# IronDue.net
KiCad netlist of a schematic drawn in EAGLE
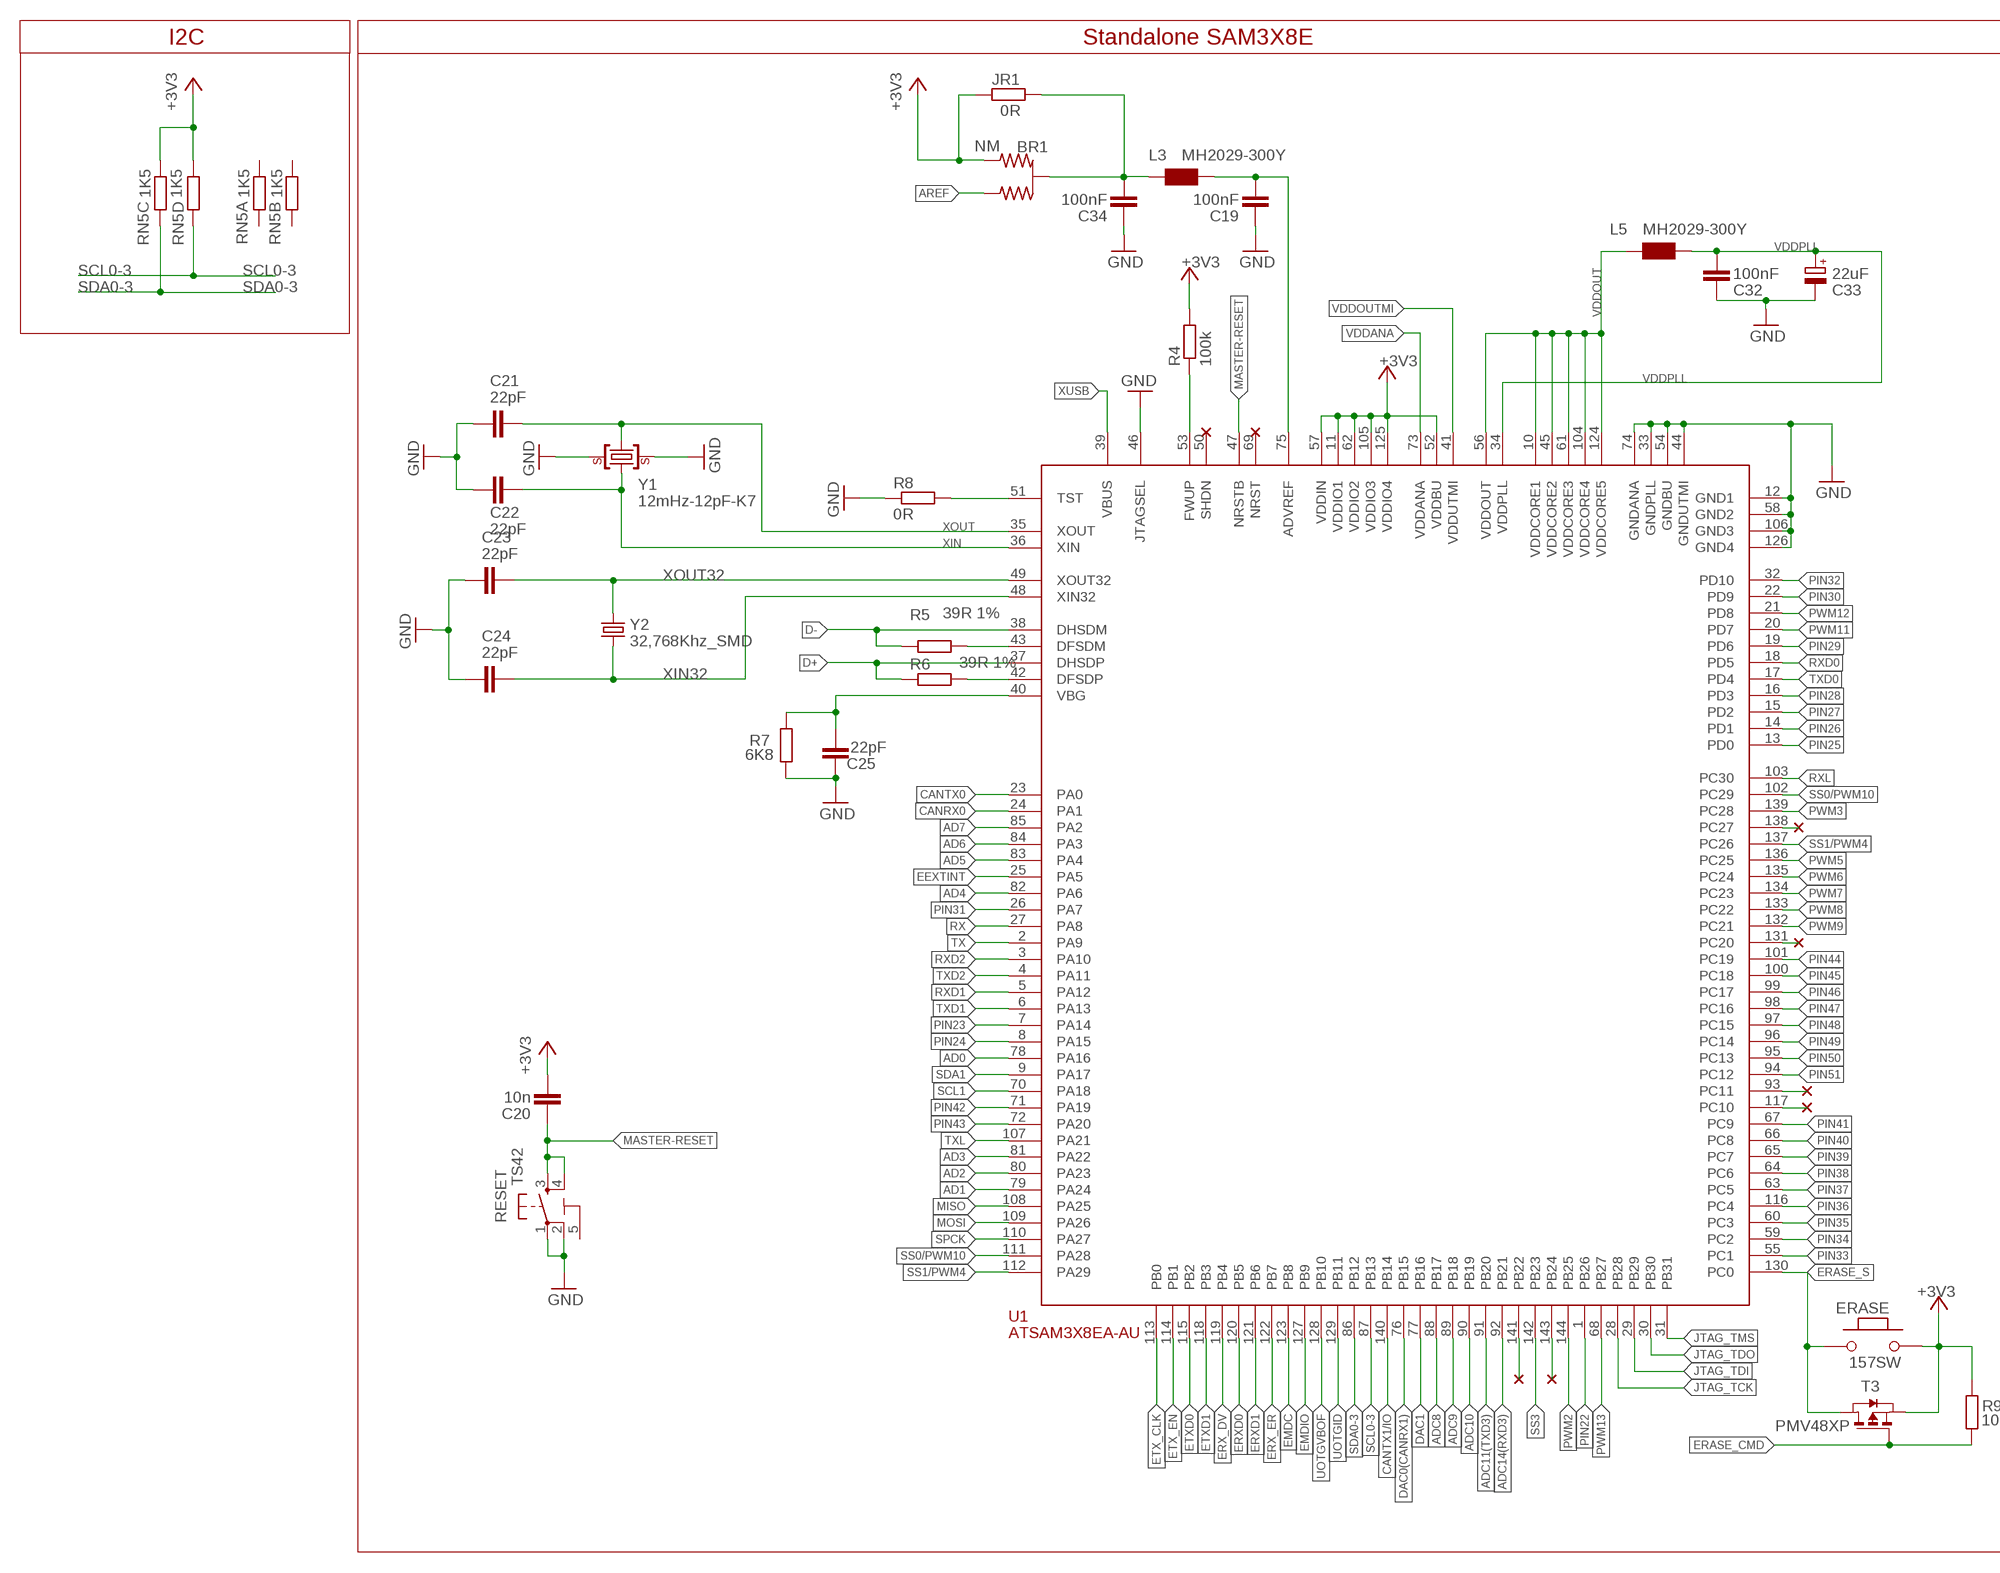
[diagram p0: schematic, sheet 1, part 1 of 2]
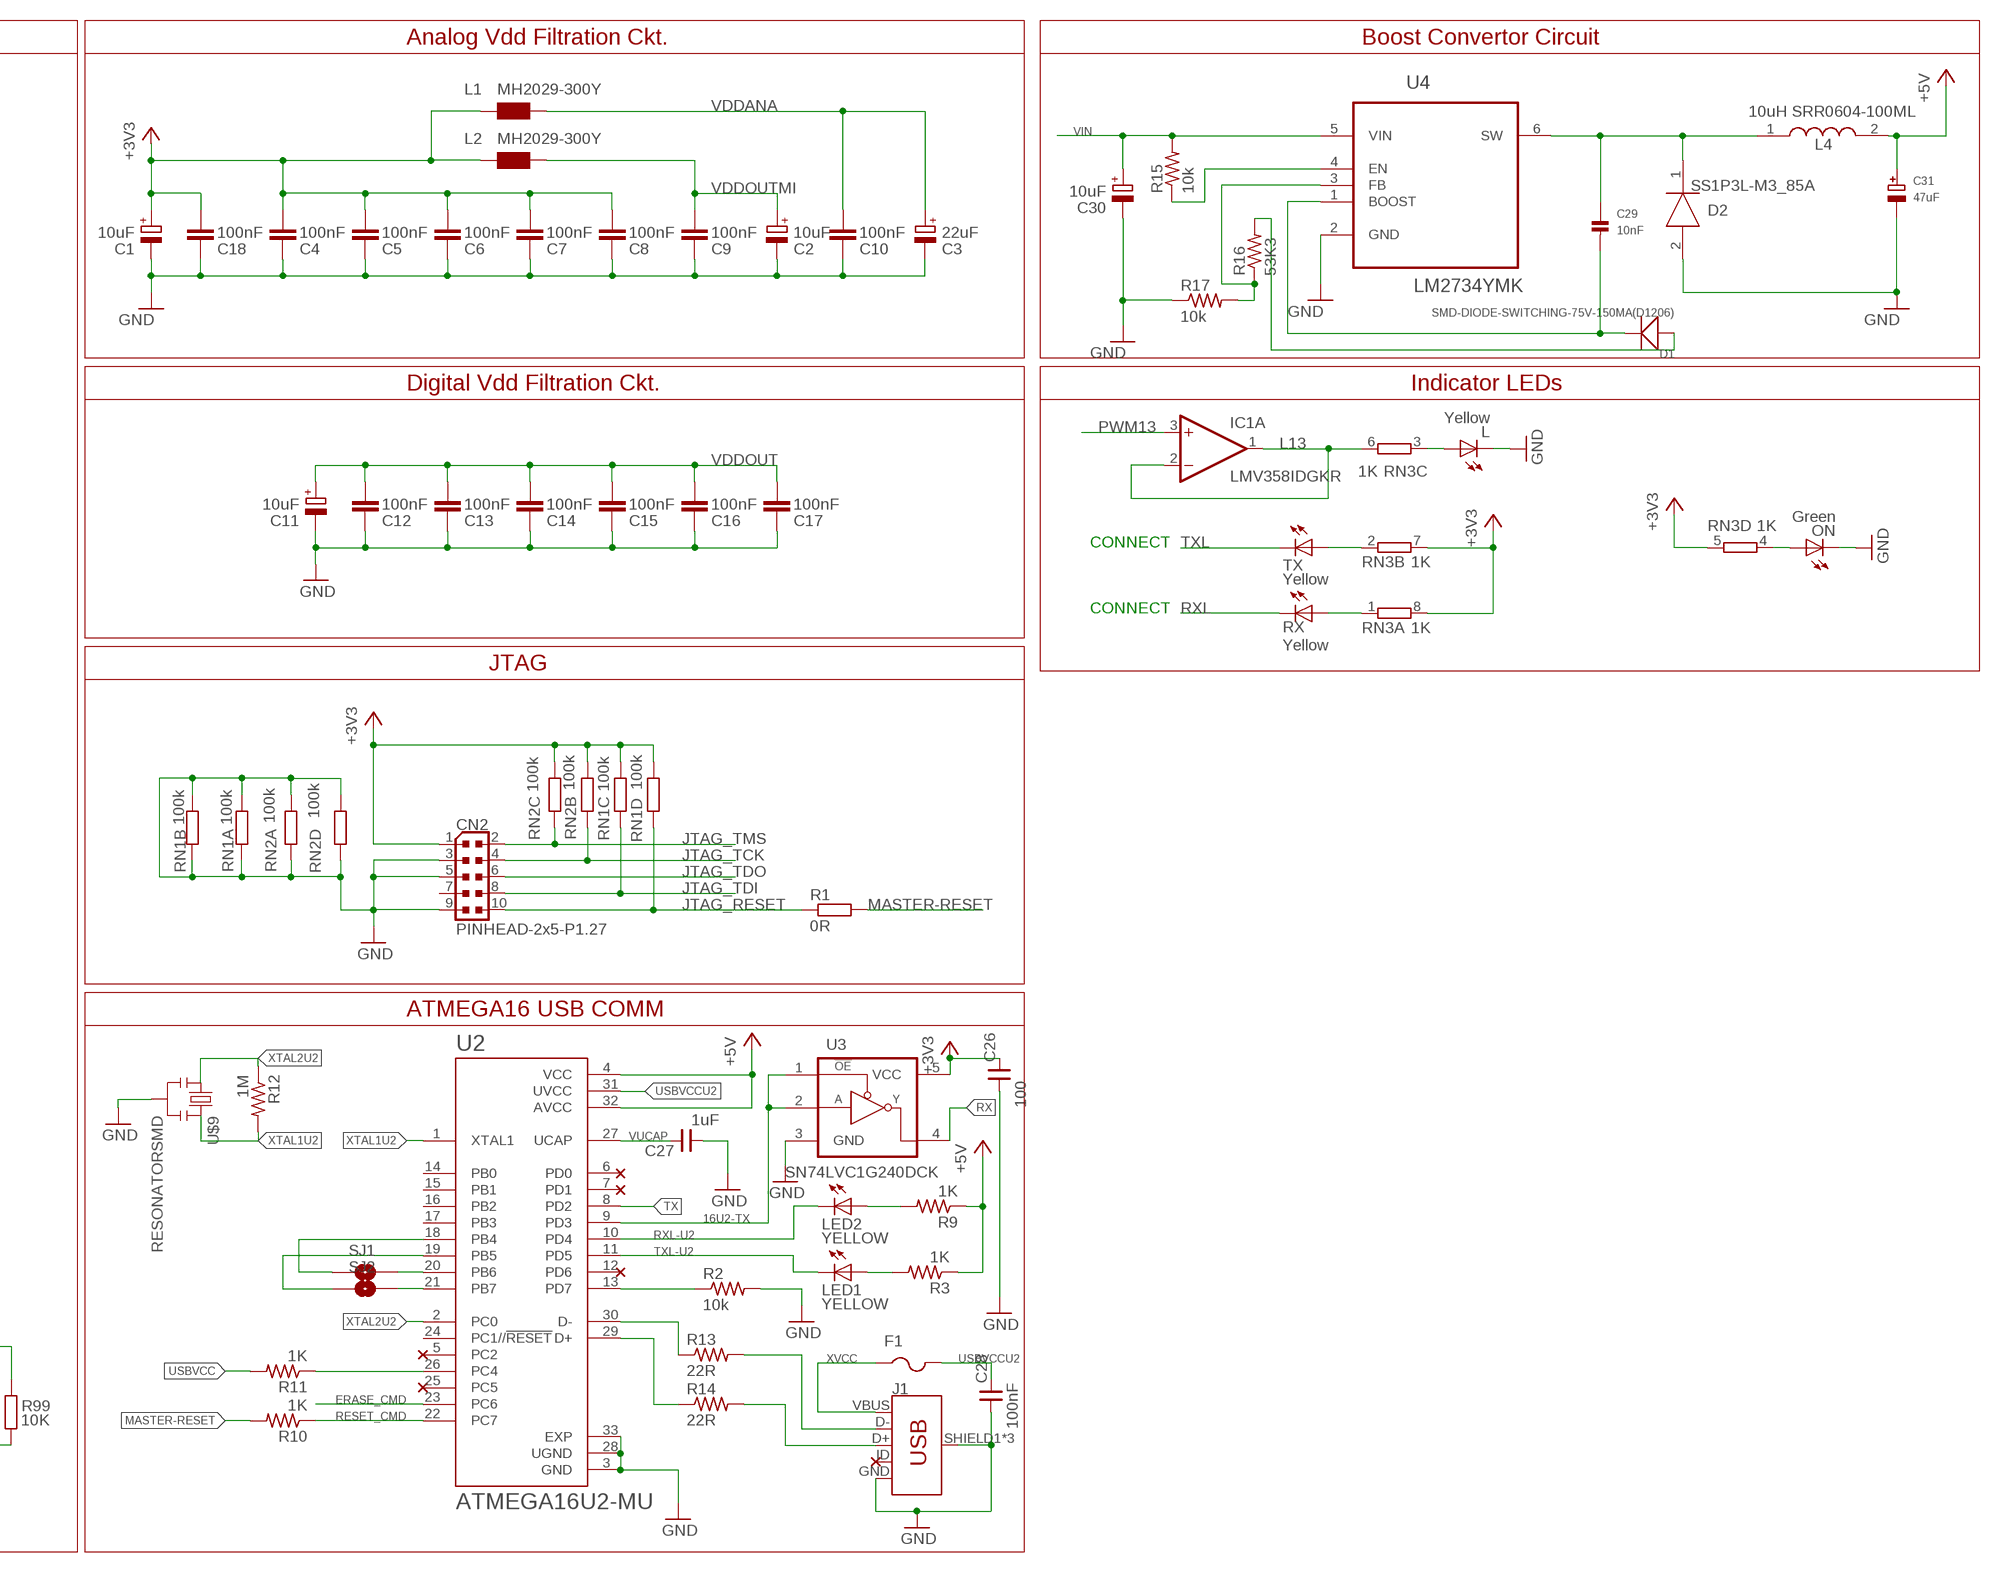
[diagram p1: schematic, sheet 1, part 2 of 2]

(export (version "E")
  (design (tool "Eeschema 10.0.6"))
  (components
    (comp (ref "BR1")
      (value "NM")
      (footprint "eagle-import:J0402")
      (libsource (lib "eagle-import") (part "J0402"))
    )
    (comp (ref "C1")
      (value "10uF")
      (footprint "eagle-import:SMC_B")
      (libsource (lib "eagle-import") (part "0167_"))
    )
    (comp (ref "C2")
      (value "10uF")
      (footprint "eagle-import:SMC_B")
      (libsource (lib "eagle-import") (part "0167_"))
    )
    (comp (ref "C3")
      (value "22uF")
      (footprint "eagle-import:SMC_B")
      (libsource (lib "eagle-import") (part "0167_"))
    )
    (comp (ref "C4")
      (value "100nF")
      (footprint "eagle-import:C0402")
      (fields (field (name "PART_NUMBER") "100nF_0402"))
      (libsource (lib "eagle-import") (part "0132_100NF_0402"))
    )
    (comp (ref "C5")
      (value "100nF")
      (footprint "eagle-import:C0402")
      (fields (field (name "PART_NUMBER") "100nF_0402"))
      (libsource (lib "eagle-import") (part "0132_100NF_0402"))
    )
    (comp (ref "C6")
      (value "100nF")
      (footprint "eagle-import:C0402")
      (fields (field (name "PART_NUMBER") "100nF_0402"))
      (libsource (lib "eagle-import") (part "0132_100NF_0402"))
    )
    (comp (ref "C7")
      (value "100nF")
      (footprint "eagle-import:C0402")
      (fields (field (name "PART_NUMBER") "100nF_0402"))
      (libsource (lib "eagle-import") (part "0132_100NF_0402"))
    )
    (comp (ref "C8")
      (value "100nF")
      (footprint "eagle-import:C0402")
      (fields (field (name "PART_NUMBER") "100nF_0402"))
      (libsource (lib "eagle-import") (part "0132_100NF_0402"))
    )
    (comp (ref "C9")
      (value "100nF")
      (footprint "eagle-import:C0402")
      (fields (field (name "PART_NUMBER") "100nF_0402"))
      (libsource (lib "eagle-import") (part "0132_100NF_0402"))
    )
    (comp (ref "C10")
      (value "100nF")
      (footprint "eagle-import:C0402")
      (fields (field (name "PART_NUMBER") "100nF_0402"))
      (libsource (lib "eagle-import") (part "0132_100NF_0402"))
    )
    (comp (ref "C11")
      (value "10uF")
      (footprint "eagle-import:SMC_B")
      (libsource (lib "eagle-import") (part "0167_"))
    )
    (comp (ref "C12")
      (value "100nF")
      (footprint "eagle-import:C0402")
      (fields (field (name "PART_NUMBER") "100nF_0402"))
      (libsource (lib "eagle-import") (part "0132_100NF_0402"))
    )
    (comp (ref "C13")
      (value "100nF")
      (footprint "eagle-import:C0402")
      (fields (field (name "PART_NUMBER") "100nF_0402"))
      (libsource (lib "eagle-import") (part "0132_100NF_0402"))
    )
    (comp (ref "C14")
      (value "100nF")
      (footprint "eagle-import:C0402")
      (fields (field (name "PART_NUMBER") "100nF_0402"))
      (libsource (lib "eagle-import") (part "0132_100NF_0402"))
    )
    (comp (ref "C15")
      (value "100nF")
      (footprint "eagle-import:C0402")
      (fields (field (name "PART_NUMBER") "100nF_0402"))
      (libsource (lib "eagle-import") (part "0132_100NF_0402"))
    )
    (comp (ref "C16")
      (value "100nF")
      (footprint "eagle-import:C0402")
      (fields (field (name "PART_NUMBER") "100nF_0402"))
      (libsource (lib "eagle-import") (part "0132_100NF_0402"))
    )
    (comp (ref "C17")
      (value "100nF")
      (footprint "eagle-import:C0402")
      (fields (field (name "PART_NUMBER") "100nF_0402"))
      (libsource (lib "eagle-import") (part "0132_100NF_0402"))
    )
    (comp (ref "C18")
      (value "100nF")
      (footprint "eagle-import:C0402")
      (fields (field (name "PART_NUMBER") "100nF_0402"))
      (libsource (lib "eagle-import") (part "0132_100NF_0402"))
    )
    (comp (ref "C19")
      (value "100nF")
      (footprint "eagle-import:C0402")
      (fields (field (name "PART_NUMBER") "100nF_0402"))
      (libsource (lib "eagle-import") (part "0132_100NF_0402"))
    )
    (comp (ref "C20")
      (value "10n")
      (footprint "eagle-import:C0402")
      (libsource (lib "eagle-import") (part "0165_10NF_0402"))
    )
    (comp (ref "C21")
      (value "22pF")
      (footprint "eagle-import:C0402")
      (fields (field (name "PART_NUMBER") "22pF_0402"))
      (libsource (lib "eagle-import") (part "0137_22PF_0402"))
    )
    (comp (ref "C22")
      (value "22pF")
      (footprint "eagle-import:C0402")
      (fields (field (name "PART_NUMBER") "22pF_0402"))
      (libsource (lib "eagle-import") (part "0137_22PF_0402"))
    )
    (comp (ref "C23")
      (value "22pF")
      (footprint "eagle-import:C0402")
      (fields (field (name "PART_NUMBER") "22pF_0402"))
      (libsource (lib "eagle-import") (part "0137_22PF_0402"))
    )
    (comp (ref "C24")
      (value "22pF")
      (footprint "eagle-import:C0402")
      (fields (field (name "PART_NUMBER") "22pF_0402"))
      (libsource (lib "eagle-import") (part "0137_22PF_0402"))
    )
    (comp (ref "C25")
      (value "22pF")
      (footprint "eagle-import:C0402")
      (fields (field (name "PART_NUMBER") "22pF_0402"))
      (libsource (lib "eagle-import") (part "0137_22PF_0402"))
    )
    (comp (ref "C26")
      (value "100")
      (footprint "eagle-import:0402")
      (libsource (lib "eagle-import") (part "CNP-0402"))
    )
    (comp (ref "C27")
      (value "1uF")
      (footprint "eagle-import:0402")
      (libsource (lib "eagle-import") (part "CNP-0402"))
    )
    (comp (ref "C28")
      (value "100nF")
      (footprint "eagle-import:0402")
      (libsource (lib "eagle-import") (part "CNP-0402"))
    )
    (comp (ref "C29")
      (value "10nF")
      (footprint "eagle-import:0402")
      (libsource (lib "eagle-import") (part "CAP_CERAMIC0402"))
    )
    (comp (ref "C30")
      (value "10uF")
      (footprint "eagle-import:SMC_B")
      (libsource (lib "eagle-import") (part "0167_"))
    )
    (comp (ref "C31")
      (value "47uF")
      (footprint "eagle-import:PANASONIC_D")
      (libsource (lib "eagle-import") (part "CAP_ELECTROLYTICPANASONIC_D"))
    )
    (comp (ref "C32")
      (value "100nF")
      (footprint "eagle-import:C0402")
      (fields (field (name "PART_NUMBER") "100nF_0402"))
      (libsource (lib "eagle-import") (part "0132_100NF_0402"))
    )
    (comp (ref "C33")
      (value "22uF")
      (footprint "eagle-import:SMC_B")
      (libsource (lib "eagle-import") (part "0167_"))
    )
    (comp (ref "C34")
      (value "100nF")
      (footprint "eagle-import:C0402")
      (fields (field (name "PART_NUMBER") "100nF_0402"))
      (libsource (lib "eagle-import") (part "0132_100NF_0402"))
    )
    (comp (ref "CN2")
      (value "PINHEAD-2x5-P1.27")
      (footprint "eagle-import:PINHEAD_2X05_127")
      (libsource (lib "eagle-import") (part "0171_PH127-205DF055G00AROUND-PADS"))
    )
    (comp (ref "D1")
      (value "SMD-DIODE-SWITCHING-75V-150MA(D1206)")
      (footprint "eagle-import:LED-1206")
      (fields (field (name "MF") "Bourns") (field (name "MP") "CD1206-S01575"))
      (libsource (lib "eagle-import") (part "SMD-DIODE-SWITCHING-75V-150MA(D1206)"))
    )
    (comp (ref "D2")
      (value "SS1P3L-M3_85A")
      (footprint "eagle-import:SMP")
      (fields
        (field (name "MANUFACTURER_PART_NUMBER") "SS1P3L-M3/85A")
        (field (name "MOUSER_PART_NUMBER") "625-SS1P3L-M3/85A")
      )
      (libsource (lib "eagle-import") (part "SS1P3L-M3_85A"))
    )
    (comp (ref "ERASE")
      (value "157SW")
      (footprint "eagle-import:SMD_157SW")
      (fields (field (name "PART_NUMBER") "IT-1185AP1C-160G-G_T&R"))
      (libsource (lib "eagle-import") (part "0173_IT-1185AP1C-160G-G_T&R"))
    )
    (comp (ref "F1")
      (value "MF-MSMF050-2 500mA")
      (footprint "eagle-import:1812")
      (libsource (lib "eagle-import") (part "PTCFUSE-1812"))
    )
    (comp (ref "IC1")
      (value "LMV358IDGKR")
      (footprint "eagle-import:MSOP08")
      (libsource (lib "eagle-import") (part "0021_LMV358IDGKR"))
    )
    (comp (ref "J1")
      (value "USB_MICRO-BREDUCED_PASTE")
      (footprint "eagle-import:USB-B-MICRO-SMD_RED_PASTE")
      (libsource (lib "eagle-import") (part "USB_MICRO-BREDUCED_PASTE"))
    )
    (comp (ref "JR1")
      (value "0R")
      (footprint "eagle-import:R0402")
      (fields (field (name "PART_NUMBER") "JUMP_0402"))
      (libsource (lib "eagle-import") (part "0039_JUMP_0402"))
    )
    (comp (ref "L")
      (value "Yellow")
      (footprint "eagle-import:CHIPLED_0805")
      (fields (field (name "PART_NUMBER") "KPT-2012YC"))
      (libsource (lib "eagle-import") (part "0044_KPT-2012YC"))
    )
    (comp (ref "L1")
      (value "MH2029-300Y")
      (footprint "eagle-import:0805")
      (fields (field (name "PART_NUMBER") "BLM21PG300SN1D_/_MH2029-300Y"))
      (libsource (lib "eagle-import") (part "0001_BLM21PG300SN1D_/_MH2029-300Y"))
    )
    (comp (ref "L2")
      (value "MH2029-300Y")
      (footprint "eagle-import:0805")
      (fields (field (name "PART_NUMBER") "BLM21PG300SN1D_/_MH2029-300Y"))
      (libsource (lib "eagle-import") (part "0001_BLM21PG300SN1D_/_MH2029-300Y"))
    )
    (comp (ref "L3")
      (value "MH2029-300Y")
      (footprint "eagle-import:0805")
      (fields (field (name "PART_NUMBER") "BLM21PG300SN1D_/_MH2029-300Y"))
      (libsource (lib "eagle-import") (part "0001_BLM21PG300SN1D_/_MH2029-300Y"))
    )
    (comp (ref "L4")
      (value "10uH SRR0604-100ML")
      (footprint "eagle-import:SRR0604-SERIES")
      (fields
        (field (name "MANUFACTURER_PART_NUMBER") "SRR0604-100ML")
        (field (name "MOUSER_PART_NUMBER") "652-SRR0604-100ML")
        (field (name "RS_PART_NUMBER") "1728488")
      )
      (libsource (lib "eagle-import") (part "SRR0604-100ML"))
    )
    (comp (ref "L5")
      (value "MH2029-300Y")
      (footprint "eagle-import:0805")
      (fields (field (name "PART_NUMBER") "BLM21PG300SN1D_/_MH2029-300Y"))
      (libsource (lib "eagle-import") (part "0001_BLM21PG300SN1D_/_MH2029-300Y"))
    )
    (comp (ref "LED1")
      (value "YELLOW")
      (footprint "eagle-import:CHIPLED_0805")
      (libsource (lib "eagle-import") (part "LEDCHIPLED_0805"))
    )
    (comp (ref "LED2")
      (value "YELLOW")
      (footprint "eagle-import:CHIPLED_0805")
      (libsource (lib "eagle-import") (part "LEDCHIPLED_0805"))
    )
    (comp (ref "ON")
      (value "Green")
      (footprint "eagle-import:CHIPLED_0805")
      (fields (field (name "PART_NUMBER") "KPT-2012SGC"))
      (libsource (lib "eagle-import") (part "0043_KPT-2012SGC"))
    )
    (comp (ref "R1")
      (value "0R")
      (footprint "eagle-import:R0402")
      (fields (field (name "PART_NUMBER") "JUMP_0402"))
      (libsource (lib "eagle-import") (part "0039_JUMP_0402"))
    )
    (comp (ref "R2")
      (value "10k")
      (footprint "eagle-import:R0402")
      (libsource (lib "eagle-import") (part "R-US_R0402"))
    )
    (comp (ref "R3")
      (value "1K")
      (footprint "eagle-import:R0402")
      (libsource (lib "eagle-import") (part "R-US_R0402"))
    )
    (comp (ref "R4")
      (value "100k")
      (footprint "eagle-import:R0402")
      (fields (field (name "PART_NUMBER") "CR0402FX1003 L"))
      (libsource (lib "eagle-import") (part "0134_CR0402FX1003L"))
    )
    (comp (ref "R5")
      (value "39R 1%")
      (footprint "eagle-import:R0402")
      (libsource (lib "eagle-import") (part "0138_39R_0402"))
    )
    (comp (ref "R6")
      (value "39R 1%")
      (footprint "eagle-import:R0402")
      (libsource (lib "eagle-import") (part "0138_39R_0402"))
    )
    (comp (ref "R7")
      (value "6K8")
      (footprint "eagle-import:R0603-ROUND")
      (fields (field (name "PART_NUMBER") "6K8_0603"))
      (libsource (lib "eagle-import") (part "0164_6K8_0603"))
    )
    (comp (ref "R8")
      (value "0R")
      (footprint "eagle-import:R0402")
      (fields (field (name "PART_NUMBER") "JUMP_0402"))
      (libsource (lib "eagle-import") (part "0039_JUMP_0402"))
    )
    (comp (ref "R9")
      (value "1K")
      (footprint "eagle-import:R0402")
      (libsource (lib "eagle-import") (part "R-US_R0402"))
    )
    (comp (ref "R10")
      (value "1K")
      (footprint "eagle-import:R0402")
      (libsource (lib "eagle-import") (part "R-US_R0402"))
    )
    (comp (ref "R11")
      (value "1K")
      (footprint "eagle-import:R0402")
      (libsource (lib "eagle-import") (part "R-US_R0402"))
    )
    (comp (ref "R12")
      (value "1M")
      (footprint "eagle-import:R0402")
      (libsource (lib "eagle-import") (part "R-US_R0402"))
    )
    (comp (ref "R13")
      (value "22R")
      (footprint "eagle-import:R0402")
      (libsource (lib "eagle-import") (part "R-US_R0402"))
    )
    (comp (ref "R14")
      (value "22R")
      (footprint "eagle-import:R0402")
      (libsource (lib "eagle-import") (part "R-US_R0402"))
    )
    (comp (ref "R15")
      (value "10k")
      (footprint "eagle-import:R0402")
      (libsource (lib "eagle-import") (part "R-US_R0402"))
    )
    (comp (ref "R16")
      (value "53K3")
      (footprint "eagle-import:R0603")
      (libsource (lib "eagle-import") (part "R-US_R0603"))
    )
    (comp (ref "R17")
      (value "10k")
      (footprint "eagle-import:R0603")
      (libsource (lib "eagle-import") (part "R-US_R0603"))
    )
    (comp (ref "R99")
      (value "10K")
      (footprint "eagle-import:R0402")
      (fields (field (name "PART_NUMBER") "CR0402FX1002_L"))
      (libsource (lib "eagle-import") (part "0136_CR0402FX1002_L"))
    )
    (comp (ref "RESET")
      (value "TS42")
      (footprint "eagle-import:TS42")
      (fields (field (name "PART_NUMBER") "IT-1157AHNP-160G-G_GTR"))
      (libsource (lib "eagle-import") (part "0946_TS42031-160W-TR-7260"))
    )
    (comp (ref "RN1")
      (value "100k")
      (footprint "eagle-import:CAY16")
      (fields (field (name "PART_NUMBER") "CAY16-104J4LF"))
      (libsource (lib "eagle-import") (part "0168_CAY16-104J4LF"))
    )
    (comp (ref "RN2")
      (value "100k")
      (footprint "eagle-import:CAY16")
      (fields (field (name "PART_NUMBER") "CAY16-104J4LF"))
      (libsource (lib "eagle-import") (part "0168_CAY16-104J4LF"))
    )
    (comp (ref "RN3")
      (value "1K")
      (footprint "eagle-import:CAY16")
      (fields (field (name "PART_NUMBER") "064R_1K_/_CAY16-102J4LF"))
      (libsource (lib "eagle-import") (part "0005_064R_1K_/_CAY16-102J4LF"))
    )
    (comp (ref "RN5")
      (value "1K5")
      (footprint "eagle-import:CAY16")
      (libsource (lib "eagle-import") (part "0163_1K5_ARRAY"))
    )
    (comp (ref "RX")
      (value "Yellow")
      (footprint "eagle-import:CHIPLED_0805")
      (fields (field (name "PART_NUMBER") "KPT-2012YC"))
      (libsource (lib "eagle-import") (part "0044_KPT-2012YC"))
    )
    (comp (ref "SJ1")
      (value "SOLDERJUMPERNO")
      (footprint "eagle-import:SJ_2S-NO")
      (libsource (lib "eagle-import") (part "SOLDERJUMPERNO"))
    )
    (comp (ref "SJ2")
      (value "SOLDERJUMPERNO")
      (footprint "eagle-import:SJ_2S-NO")
      (libsource (lib "eagle-import") (part "SOLDERJUMPERNO"))
    )
    (comp (ref "T3")
      (value "PMV48XP")
      (footprint "eagle-import:SOT-23")
      (libsource (lib "eagle-import") (part "0297_PMV48XP"))
    )
    (comp (ref "TX")
      (value "Yellow")
      (footprint "eagle-import:CHIPLED_0805")
      (fields (field (name "PART_NUMBER") "KPT-2012YC"))
      (libsource (lib "eagle-import") (part "0044_KPT-2012YC"))
    )
    (comp (ref "U$1") (value "NC") (footprint "eagle-import:NC") (libsource (lib "eagle-import") (part "NC")))
    (comp (ref "U$2") (value "NC") (footprint "eagle-import:NC") (libsource (lib "eagle-import") (part "NC")))
    (comp (ref "U$3") (value "NC") (footprint "eagle-import:NC") (libsource (lib "eagle-import") (part "NC")))
    (comp (ref "U$4") (value "NC") (footprint "eagle-import:NC") (libsource (lib "eagle-import") (part "NC")))
    (comp (ref "U$5") (value "NC") (footprint "eagle-import:NC") (libsource (lib "eagle-import") (part "NC")))
    (comp (ref "U$6") (value "NC") (footprint "eagle-import:NC") (libsource (lib "eagle-import") (part "NC")))
    (comp (ref "U$7") (value "NC") (footprint "eagle-import:NC") (libsource (lib "eagle-import") (part "NC")))
    (comp (ref "U$8") (value "NC") (footprint "eagle-import:NC") (libsource (lib "eagle-import") (part "NC")))
    (comp (ref "U$9")
      (value "RESONATORSMD")
      (footprint "eagle-import:RESONATOR-SMD")
      (libsource (lib "eagle-import") (part "RESONATORSMD"))
    )
    (comp (ref "U$10")
      (value "NC")
      (footprint "eagle-import:NC")
      (libsource (lib "eagle-import") (part "NC"))
    )
    (comp (ref "U$11")
      (value "NC")
      (footprint "eagle-import:NC")
      (libsource (lib "eagle-import") (part "NC"))
    )
    (comp (ref "U$12")
      (value "NC")
      (footprint "eagle-import:NC")
      (libsource (lib "eagle-import") (part "NC"))
    )
    (comp (ref "U$13")
      (value "NC")
      (footprint "eagle-import:NC")
      (libsource (lib "eagle-import") (part "NC"))
    )
    (comp (ref "U$14")
      (value "NC")
      (footprint "eagle-import:NC")
      (libsource (lib "eagle-import") (part "NC"))
    )
    (comp (ref "U$15")
      (value "NC")
      (footprint "eagle-import:NC")
      (libsource (lib "eagle-import") (part "NC"))
    )
    (comp (ref "U1")
      (value "ATSAM3X8EA-AU")
      (footprint "eagle-import:LQFP144")
      (libsource (lib "eagle-import") (part "0162_ATSAM3X8EA-AUAU"))
    )
    (comp (ref "U2")
      (value "ATMEGA16U2-MU")
      (footprint "eagle-import:QFN50P500X500X100-33N")
      (fields (field (name "MF") "Microchip"))
      (libsource (lib "eagle-import") (part "ATMEGA16U2-MU"))
    )
    (comp (ref "U3")
      (value "SN74LVC1G240DCK")
      (footprint "eagle-import:SC70-5")
      (libsource (lib "eagle-import") (part "SN74LVC1G240DCK"))
    )
    (comp (ref "U4")
      (value "LM2734YMK")
      (footprint "eagle-import:SOT95P285X100-6N")
      (fields (field (name "MF") "Texas Instruments") (field (name "MP") "LM2734YMK/NOPB"))
      (libsource (lib "eagle-import") (part "LM2734YMK"))
    )
    (comp (ref "Y1")
      (value "12mHz-12pF-K7")
      (footprint "eagle-import:CRYSTAL-3.2-2.5")
      (libsource (lib "eagle-import") (part "0396_12MHZ-12PF-K7"))
    )
    (comp (ref "Y2")
      (value "32,768Khz_SMD")
      (footprint "eagle-import:RESONATOR_EPSON_FC_145")
      (fields (field (name "PART_NUMBER") "ABS07-32.768KHZ-T"))
      (libsource (lib "eagle-import") (part "0213_ABS07-32.768KHZ-T"))
    )
  )
  (nets
    (net (code "1") (name "+3V3") (class "Default")
      (node (ref "BR1") (pin "3") (pinfunction "2_3") (pintype "passive"))
      (node (ref "C1") (pin "+") (pinfunction "+_+") (pintype "passive"))
      (node (ref "C18") (pin "2") (pinfunction "2_2") (pintype "passive"))
      (node (ref "C20") (pin "2") (pinfunction "2_2") (pintype "passive"))
      (node (ref "C26") (pin "2") (pinfunction "2_2") (pintype "passive"))
      (node (ref "C4") (pin "2") (pinfunction "2_2") (pintype "passive"))
      (node (ref "C5") (pin "2") (pinfunction "2_2") (pintype "passive"))
      (node (ref "C6") (pin "2") (pinfunction "2_2") (pintype "passive"))
      (node (ref "C7") (pin "2") (pinfunction "2_2") (pintype "passive"))
      (node (ref "C8") (pin "2") (pinfunction "2_2") (pintype "passive"))
      (node (ref "CN2") (pin "1") (pinfunction "1_1") (pintype "passive"))
      (node (ref "ERASE") (pin "1") (pinfunction "1_1") (pintype "passive"))
      (node (ref "JR1") (pin "1") (pinfunction "1_1") (pintype "passive"))
      (node (ref "L1") (pin "1") (pinfunction "1_1") (pintype "passive"))
      (node (ref "L2") (pin "1") (pinfunction "1_1") (pintype "passive"))
      (node (ref "R4") (pin "2") (pinfunction "2_2") (pintype "passive"))
      (node (ref "R99") (pin "2") (pinfunction "2_2") (pintype "passive"))
      (node (ref "RN1") (pin "5") (pinfunction "2_5") (pintype "passive"))
      (node (ref "RN1") (pin "6") (pinfunction "2_6") (pintype "passive"))
      (node (ref "RN2") (pin "2") (pinfunction "1_2") (pintype "passive"))
      (node (ref "RN2") (pin "3") (pinfunction "1_3") (pintype "passive"))
      (node (ref "RN3") (pin "5") (pinfunction "2_5") (pintype "passive"))
      (node (ref "RN3") (pin "7") (pinfunction "2_7") (pintype "passive"))
      (node (ref "RN3") (pin "8") (pinfunction "2_8") (pintype "passive"))
      (node (ref "RN5") (pin "3") (pinfunction "1_3") (pintype "passive"))
      (node (ref "RN5") (pin "4") (pinfunction "1_4") (pintype "passive"))
      (node (ref "T3") (pin "2") (pinfunction "S_2") (pintype "passive"))
      (node (ref "U1") (pin "105") (pinfunction "VDDIO3_105") (pintype "power_in"))
      (node (ref "U1") (pin "11") (pinfunction "VDDIO1_11") (pintype "power_in"))
      (node (ref "U1") (pin "125") (pinfunction "VDDIO4_125") (pintype "power_in"))
      (node (ref "U1") (pin "52") (pinfunction "VDDBU_52") (pintype "power_in"))
      (node (ref "U1") (pin "57") (pinfunction "VDDIN_57") (pintype "power_in"))
      (node (ref "U1") (pin "62") (pinfunction "VDDIO2_62") (pintype "power_in"))
      (node (ref "U3") (pin "5") (pinfunction "VCC_5") (pintype "power_in"))
    )
    (net (code "2") (name "+5V") (class "Default")
      (node (ref "C31") (pin "+") (pinfunction "+_+") (pintype "passive"))
      (node (ref "L4") (pin "2") (pinfunction "2_2") (pintype "bidirectional"))
      (node (ref "R3") (pin "1") (pinfunction "1_1") (pintype "passive"))
      (node (ref "R9") (pin "1") (pinfunction "1_1") (pintype "passive"))
      (node (ref "U2") (pin "32") (pinfunction "AVCC_32") (pintype "power_in"))
      (node (ref "U2") (pin "4") (pinfunction "VCC_4") (pintype "power_in"))
    )
    (net (code "3") (name "/5-GND") (class "Default")
      (node (ref "RESET") (pin "5") (pinfunction "5-GND_5") (pintype "power_in"))
    )
    (net (code "4") (name "/16U2-TX") (class "Default")
      (node (ref "U2") (pin "9") (pinfunction "PD3_9") (pintype "bidirectional"))
      (node (ref "U3") (pin "1") (pinfunction "OE#_1") (pintype "input"))
      (node (ref "U3") (pin "2") (pinfunction "A_2") (pintype "input"))
    )
    (net (code "5") (name "/JTAG_RESET") (class "Default")
      (node (ref "CN2") (pin "10") (pinfunction "10_10") (pintype "passive"))
      (node (ref "R1") (pin "1") (pinfunction "1_1") (pintype "passive"))
      (node (ref "RN1") (pin "4") (pinfunction "1_4") (pintype "passive"))
    )
    (net (code "6") (name "/L13") (class "Default")
      (node (ref "IC1") (pin "1") (pinfunction "OUT_1") (pintype "output"))
      (node (ref "IC1") (pin "2") (pinfunction "-IN_2") (pintype "input"))
      (node (ref "RN3") (pin "6") (pinfunction "2_6") (pintype "passive"))
    )
    (net (code "7") (name "/RESET_CMD") (class "Default")
      (node (ref "R10") (pin "1") (pinfunction "1_1") (pintype "passive"))
      (node (ref "U2") (pin "22") (pinfunction "PC7_22") (pintype "bidirectional"))
    )
    (net (code "8") (name "/RXL-U2") (class "Default")
      (node (ref "LED2") (pin "C") (pinfunction "C_C") (pintype "passive"))
      (node (ref "U2") (pin "10") (pinfunction "PD4_10") (pintype "bidirectional"))
    )
    (net (code "9") (name "/TXL-U2") (class "Default")
      (node (ref "LED1") (pin "C") (pinfunction "C_C") (pintype "passive"))
      (node (ref "U2") (pin "11") (pinfunction "PD5_11") (pintype "bidirectional"))
    )
    (net (code "10") (name "/VDDOUT") (class "Default")
      (node (ref "C11") (pin "+") (pinfunction "+_+") (pintype "passive"))
      (node (ref "C12") (pin "2") (pinfunction "2_2") (pintype "passive"))
      (node (ref "C13") (pin "2") (pinfunction "2_2") (pintype "passive"))
      (node (ref "C14") (pin "2") (pinfunction "2_2") (pintype "passive"))
      (node (ref "C15") (pin "2") (pinfunction "2_2") (pintype "passive"))
      (node (ref "C16") (pin "2") (pinfunction "2_2") (pintype "passive"))
      (node (ref "C17") (pin "2") (pinfunction "2_2") (pintype "passive"))
      (node (ref "L5") (pin "1") (pinfunction "1_1") (pintype "passive"))
      (node (ref "U1") (pin "10") (pinfunction "VDDCORE1_10") (pintype "input"))
      (node (ref "U1") (pin "104") (pinfunction "VDDCORE4_104") (pintype "input"))
      (node (ref "U1") (pin "124") (pinfunction "VDDCORE5_124") (pintype "input"))
      (node (ref "U1") (pin "45") (pinfunction "VDDCORE2_45") (pintype "input"))
      (node (ref "U1") (pin "56") (pinfunction "VDDOUT_56") (pintype "output"))
      (node (ref "U1") (pin "61") (pinfunction "VDDCORE3_61") (pintype "input"))
    )
    (net (code "11") (name "/VDDPLL") (class "Default")
      (node (ref "C32") (pin "2") (pinfunction "2_2") (pintype "passive"))
      (node (ref "C33") (pin "+") (pinfunction "+_+") (pintype "passive"))
      (node (ref "L5") (pin "2") (pinfunction "2_2") (pintype "passive"))
      (node (ref "U1") (pin "34") (pinfunction "VDDPLL_34") (pintype "input"))
    )
    (net (code "12") (name "/VIN") (class "Default")
      (node (ref "C30") (pin "+") (pinfunction "+_+") (pintype "passive"))
      (node (ref "R15") (pin "2") (pinfunction "2_2") (pintype "passive"))
      (node (ref "U4") (pin "5") (pinfunction "VIN_5") (pintype "power_in"))
    )
    (net (code "13") (name "/VUCAP") (class "Default")
      (node (ref "C27") (pin "2") (pinfunction "2_2") (pintype "passive"))
      (node (ref "U2") (pin "27") (pinfunction "UCAP_27") (pintype "output"))
    )
    (net (code "14") (name "/XIN") (class "Default")
      (node (ref "C22") (pin "1") (pinfunction "1_1") (pintype "passive"))
      (node (ref "U1") (pin "36") (pinfunction "XIN_36") (pintype "input"))
      (node (ref "Y1") (pin "1") (pinfunction "C1_1") (pintype "passive"))
    )
    (net (code "15") (name "/XIN32") (class "Default")
      (node (ref "C24") (pin "1") (pinfunction "1_1") (pintype "passive"))
      (node (ref "U1") (pin "48") (pinfunction "XIN32_48") (pintype "output"))
      (node (ref "Y2") (pin "P$2") (pinfunction "2_P$2") (pintype "bidirectional"))
    )
    (net (code "16") (name "/XOUT") (class "Default")
      (node (ref "C21") (pin "1") (pinfunction "1_1") (pintype "passive"))
      (node (ref "U1") (pin "35") (pinfunction "XOUT_35") (pintype "output"))
      (node (ref "Y1") (pin "3") (pinfunction "C2_3") (pintype "passive"))
    )
    (net (code "17") (name "/XOUT32") (class "Default")
      (node (ref "C23") (pin "1") (pinfunction "1_1") (pintype "passive"))
      (node (ref "U1") (pin "49") (pinfunction "XOUT32_49") (pintype "output"))
      (node (ref "Y2") (pin "P$1") (pinfunction "1_P$1") (pintype "bidirectional"))
    )
    (net (code "18") (name "/XVCC") (class "Default")
      (node (ref "F1") (pin "1") (pinfunction "1_1") (pintype "passive"))
      (node (ref "J1") (pin "VBUS") (pinfunction "VBUS_VBUS") (pintype "power_in"))
    )
    (net (code "19") (name "AD0") (class "Default")
      (node (ref "U1") (pin "78") (pinfunction "PA16_78") (pintype "bidirectional"))
    )
    (net (code "20") (name "AD1") (class "Default")
      (node (ref "U1") (pin "79") (pinfunction "PA24_79") (pintype "bidirectional"))
    )
    (net (code "21") (name "AD2") (class "Default")
      (node (ref "U1") (pin "80") (pinfunction "PA23_80") (pintype "bidirectional"))
    )
    (net (code "22") (name "AD3") (class "Default")
      (node (ref "U1") (pin "81") (pinfunction "PA22_81") (pintype "bidirectional"))
    )
    (net (code "23") (name "AD4") (class "Default")
      (node (ref "U1") (pin "82") (pinfunction "PA6_82") (pintype "bidirectional"))
    )
    (net (code "24") (name "AD5") (class "Default")
      (node (ref "U1") (pin "83") (pinfunction "PA4_83") (pintype "bidirectional"))
    )
    (net (code "25") (name "AD6") (class "Default")
      (node (ref "U1") (pin "84") (pinfunction "PA3_84") (pintype "bidirectional"))
    )
    (net (code "26") (name "AD7") (class "Default")
      (node (ref "U1") (pin "85") (pinfunction "PA2_85") (pintype "bidirectional"))
    )
    (net (code "27") (name "ADC8") (class "Default")
      (node (ref "U1") (pin "88") (pinfunction "PB17_88") (pintype "bidirectional"))
    )
    (net (code "28") (name "ADC9") (class "Default")
      (node (ref "U1") (pin "89") (pinfunction "PB18_89") (pintype "bidirectional"))
    )
    (net (code "29") (name "ADC10") (class "Default")
      (node (ref "U1") (pin "90") (pinfunction "PB19_90") (pintype "bidirectional"))
    )
    (net (code "30") (name "ADC11(TXD3)") (class "Default")
      (node (ref "U1") (pin "91") (pinfunction "PB20_91") (pintype "bidirectional"))
    )
    (net (code "31") (name "ADC14(RXD3)") (class "Default")
      (node (ref "U1") (pin "92") (pinfunction "PB21_92") (pintype "bidirectional"))
    )
    (net (code "32") (name "AREF") (class "Default")
      (node (ref "BR1") (pin "1") (pinfunction "1_1") (pintype "passive"))
    )
    (net (code "33") (name "CANRX0") (class "Default")
      (node (ref "U1") (pin "24") (pinfunction "PA1_24") (pintype "bidirectional"))
    )
    (net (code "34") (name "CANTX0") (class "Default")
      (node (ref "U1") (pin "23") (pinfunction "PA0_23") (pintype "bidirectional"))
    )
    (net (code "35") (name "CANTX1{slash}IO") (class "Default")
      (node (ref "U1") (pin "140") (pinfunction "PB14_140") (pintype "bidirectional"))
    )
    (net (code "36") (name "D+") (class "Default")
      (node (ref "R6") (pin "1") (pinfunction "1_1") (pintype "passive"))
      (node (ref "U1") (pin "37") (pinfunction "DHSDP_37") (pintype "bidirectional"))
    )
    (net (code "37") (name "D-") (class "Default")
      (node (ref "R5") (pin "1") (pinfunction "1_1") (pintype "passive"))
      (node (ref "U1") (pin "38") (pinfunction "DHSDM_38") (pintype "bidirectional"))
    )
    (net (code "38") (name "DAC0(CANRX1)") (class "Default")
      (node (ref "U1") (pin "76") (pinfunction "PB15_76") (pintype "bidirectional"))
    )
    (net (code "39") (name "DAC1") (class "Default")
      (node (ref "U1") (pin "77") (pinfunction "PB16_77") (pintype "bidirectional"))
    )
    (net (code "40") (name "EEXTINT") (class "Default")
      (node (ref "U1") (pin "25") (pinfunction "PA5_25") (pintype "bidirectional"))
    )
    (net (code "41") (name "EMDC") (class "Default")
      (node (ref "U1") (pin "123") (pinfunction "PB8_123") (pintype "bidirectional"))
    )
    (net (code "42") (name "EMDIO") (class "Default")
      (node (ref "U1") (pin "127") (pinfunction "PB9_127") (pintype "bidirectional"))
    )
    (net (code "43") (name "ERASE_CMD") (class "Default")
      (node (ref "R99") (pin "1") (pinfunction "1_1") (pintype "passive"))
      (node (ref "T3") (pin "3") (pinfunction "G_3") (pintype "passive"))
      (node (ref "U2") (pin "23") (pinfunction "PC6_23") (pintype "bidirectional"))
    )
    (net (code "44") (name "ERASE_S") (class "Default")
      (node (ref "ERASE") (pin "2") (pinfunction "2_2") (pintype "passive"))
      (node (ref "T3") (pin "1") (pinfunction "D_1") (pintype "passive"))
      (node (ref "U1") (pin "130") (pinfunction "PC0_130") (pintype "bidirectional"))
    )
    (net (code "45") (name "ERXD0") (class "Default")
      (node (ref "U1") (pin "120") (pinfunction "PB5_120") (pintype "bidirectional"))
    )
    (net (code "46") (name "ERXD1") (class "Default")
      (node (ref "U1") (pin "121") (pinfunction "PB6_121") (pintype "bidirectional"))
    )
    (net (code "47") (name "ERX_DV") (class "Default")
      (node (ref "U1") (pin "119") (pinfunction "PB4_119") (pintype "bidirectional"))
    )
    (net (code "48") (name "ERX_ER") (class "Default")
      (node (ref "U1") (pin "122") (pinfunction "PB7_122") (pintype "bidirectional"))
    )
    (net (code "49") (name "ETXD0") (class "Default")
      (node (ref "U1") (pin "115") (pinfunction "PB2_115") (pintype "bidirectional"))
    )
    (net (code "50") (name "ETXD1") (class "Default")
      (node (ref "U1") (pin "118") (pinfunction "PB3_118") (pintype "bidirectional"))
    )
    (net (code "51") (name "ETX_CLK") (class "Default")
      (node (ref "U1") (pin "113") (pinfunction "PB0_113") (pintype "bidirectional"))
    )
    (net (code "52") (name "ETX_EN") (class "Default")
      (node (ref "U1") (pin "114") (pinfunction "PB1_114") (pintype "bidirectional"))
    )
    (net (code "53") (name "GND") (class "Default")
      (node (ref "C1") (pin "-") (pinfunction "-_-") (pintype "passive"))
      (node (ref "C10") (pin "1") (pinfunction "1_1") (pintype "passive"))
      (node (ref "C11") (pin "-") (pinfunction "-_-") (pintype "passive"))
      (node (ref "C12") (pin "1") (pinfunction "1_1") (pintype "passive"))
      (node (ref "C13") (pin "1") (pinfunction "1_1") (pintype "passive"))
      (node (ref "C14") (pin "1") (pinfunction "1_1") (pintype "passive"))
      (node (ref "C15") (pin "1") (pinfunction "1_1") (pintype "passive"))
      (node (ref "C16") (pin "1") (pinfunction "1_1") (pintype "passive"))
      (node (ref "C17") (pin "1") (pinfunction "1_1") (pintype "passive"))
      (node (ref "C18") (pin "1") (pinfunction "1_1") (pintype "passive"))
      (node (ref "C19") (pin "1") (pinfunction "1_1") (pintype "passive"))
      (node (ref "C2") (pin "-") (pinfunction "-_-") (pintype "passive"))
      (node (ref "C21") (pin "2") (pinfunction "2_2") (pintype "passive"))
      (node (ref "C22") (pin "2") (pinfunction "2_2") (pintype "passive"))
      (node (ref "C23") (pin "2") (pinfunction "2_2") (pintype "passive"))
      (node (ref "C24") (pin "2") (pinfunction "2_2") (pintype "passive"))
      (node (ref "C25") (pin "2") (pinfunction "2_2") (pintype "passive"))
      (node (ref "C26") (pin "1") (pinfunction "1_1") (pintype "passive"))
      (node (ref "C27") (pin "1") (pinfunction "1_1") (pintype "passive"))
      (node (ref "C28") (pin "1") (pinfunction "1_1") (pintype "passive"))
      (node (ref "C3") (pin "-") (pinfunction "-_-") (pintype "passive"))
      (node (ref "C30") (pin "-") (pinfunction "-_-") (pintype "passive"))
      (node (ref "C31") (pin "-") (pinfunction "-_-") (pintype "passive"))
      (node (ref "C32") (pin "1") (pinfunction "1_1") (pintype "passive"))
      (node (ref "C33") (pin "-") (pinfunction "-_-") (pintype "passive"))
      (node (ref "C34") (pin "1") (pinfunction "1_1") (pintype "passive"))
      (node (ref "C4") (pin "1") (pinfunction "1_1") (pintype "passive"))
      (node (ref "C5") (pin "1") (pinfunction "1_1") (pintype "passive"))
      (node (ref "C6") (pin "1") (pinfunction "1_1") (pintype "passive"))
      (node (ref "C7") (pin "1") (pinfunction "1_1") (pintype "passive"))
      (node (ref "C8") (pin "1") (pinfunction "1_1") (pintype "passive"))
      (node (ref "C9") (pin "1") (pinfunction "1_1") (pintype "passive"))
      (node (ref "CN2") (pin "3") (pinfunction "3_3") (pintype "passive"))
      (node (ref "CN2") (pin "5") (pinfunction "5_5") (pintype "passive"))
      (node (ref "CN2") (pin "9") (pinfunction "9_9") (pintype "passive"))
      (node (ref "D2") (pin "2") (pinfunction "K_2") (pintype "bidirectional"))
      (node (ref "J1") (pin "GND") (pinfunction "GND_GND") (pintype "power_in"))
      (node (ref "J1") (pin "SHIELD1") (pinfunction "SHIELD_SHIELD1") (pintype "bidirectional"))
      (node (ref "J1") (pin "SHIELD2") (pinfunction "SHIELD_SHIELD2") (pintype "bidirectional"))
      (node (ref "J1") (pin "SHIELD3") (pinfunction "SHIELD_SHIELD3") (pintype "bidirectional"))
      (node (ref "L") (pin "C") (pinfunction "C_C") (pintype "passive"))
      (node (ref "ON") (pin "C") (pinfunction "C_C") (pintype "passive"))
      (node (ref "R17") (pin "1") (pinfunction "1_1") (pintype "passive"))
      (node (ref "R2") (pin "2") (pinfunction "2_2") (pintype "passive"))
      (node (ref "R7") (pin "1") (pinfunction "1_1") (pintype "passive"))
      (node (ref "R8") (pin "1") (pinfunction "1_1") (pintype "passive"))
      (node (ref "RESET") (pin "1") (pinfunction "1_1") (pintype "passive"))
      (node (ref "RESET") (pin "2") (pinfunction "2_2") (pintype "passive"))
      (node (ref "RN1") (pin "1") (pinfunction "1_1") (pintype "passive"))
      (node (ref "RN1") (pin "2") (pinfunction "1_2") (pintype "passive"))
      (node (ref "RN1") (pin "7") (pinfunction "2_7") (pintype "passive"))
      (node (ref "RN1") (pin "8") (pinfunction "2_8") (pintype "passive"))
      (node (ref "RN2") (pin "1") (pinfunction "1_1") (pintype "passive"))
      (node (ref "RN2") (pin "4") (pinfunction "1_4") (pintype "passive"))
      (node (ref "RN2") (pin "5") (pinfunction "2_5") (pintype "passive"))
      (node (ref "RN2") (pin "8") (pinfunction "2_8") (pintype "passive"))
      (node (ref "U$9") (pin "2") (pinfunction "2_2") (pintype "passive"))
      (node (ref "U1") (pin "106") (pinfunction "GND3_106") (pintype "power_in"))
      (node (ref "U1") (pin "12") (pinfunction "GND1_12") (pintype "power_in"))
      (node (ref "U1") (pin "126") (pinfunction "GND4_126") (pintype "power_in"))
      (node (ref "U1") (pin "33") (pinfunction "GNDPLL_33") (pintype "power_in"))
      (node (ref "U1") (pin "44") (pinfunction "GNDUTMI_44") (pintype "power_in"))
      (node (ref "U1") (pin "46") (pinfunction "JTAGSEL_46") (pintype "input"))
      (node (ref "U1") (pin "54") (pinfunction "GNDBU_54") (pintype "power_in"))
      (node (ref "U1") (pin "58") (pinfunction "GND2_58") (pintype "power_in"))
      (node (ref "U1") (pin "74") (pinfunction "GNDANA_74") (pintype "power_in"))
      (node (ref "U2") (pin "28") (pinfunction "UGND_28") (pintype "power_in"))
      (node (ref "U2") (pin "3") (pinfunction "GND_3") (pintype "power_in"))
      (node (ref "U2") (pin "33") (pinfunction "EXP_33") (pintype "power_in"))
      (node (ref "U3") (pin "3") (pinfunction "GND_3") (pintype "power_in"))
      (node (ref "U4") (pin "2") (pinfunction "GND_2") (pintype "passive"))
      (node (ref "Y1") (pin "2") (pinfunction "GND_2") (pintype "passive"))
      (node (ref "Y1") (pin "4") (pinfunction "GND_4") (pintype "passive"))
    )
    (net (code "54") (name "JTAG_TCK") (class "Default")
      (node (ref "CN2") (pin "4") (pinfunction "4_4") (pintype "passive"))
      (node (ref "RN2") (pin "7") (pinfunction "2_7") (pintype "passive"))
      (node (ref "U1") (pin "28") (pinfunction "PB28_28") (pintype "bidirectional"))
    )
    (net (code "55") (name "JTAG_TDI") (class "Default")
      (node (ref "CN2") (pin "8") (pinfunction "8_8") (pintype "passive"))
      (node (ref "RN1") (pin "3") (pinfunction "1_3") (pintype "passive"))
      (node (ref "U1") (pin "29") (pinfunction "PB29_29") (pintype "bidirectional"))
    )
    (net (code "56") (name "JTAG_TDO") (class "Default")
      (node (ref "CN2") (pin "6") (pinfunction "6_6") (pintype "passive"))
      (node (ref "U1") (pin "30") (pinfunction "PB30_30") (pintype "bidirectional"))
    )
    (net (code "57") (name "JTAG_TMS") (class "Default")
      (node (ref "CN2") (pin "2") (pinfunction "2_2") (pintype "passive"))
      (node (ref "RN2") (pin "6") (pinfunction "2_6") (pintype "passive"))
      (node (ref "U1") (pin "31") (pinfunction "PB31_31") (pintype "bidirectional"))
    )
    (net (code "58") (name "MASTER-RESET") (class "Default")
      (node (ref "C20") (pin "1") (pinfunction "1_1") (pintype "passive"))
      (node (ref "R1") (pin "2") (pinfunction "2_2") (pintype "passive"))
      (node (ref "R10") (pin "2") (pinfunction "2_2") (pintype "passive"))
      (node (ref "RESET") (pin "3") (pinfunction "3_3") (pintype "passive"))
      (node (ref "RESET") (pin "4") (pinfunction "4_4") (pintype "passive"))
      (node (ref "U1") (pin "47") (pinfunction "NRSTB_47") (pintype "input"))
    )
    (net (code "59") (name "MISO") (class "Default")
      (node (ref "U1") (pin "108") (pinfunction "PA25_108") (pintype "bidirectional"))
    )
    (net (code "60") (name "MOSI") (class "Default")
      (node (ref "U1") (pin "109") (pinfunction "PA26_109") (pintype "bidirectional"))
    )
    (net (code "61") (name "Net-(BR1-C)") (class "Default")
      (node (ref "BR1") (pin "2") (pinfunction "C_2") (pintype "passive"))
      (node (ref "C34") (pin "2") (pinfunction "2_2") (pintype "passive"))
      (node (ref "JR1") (pin "2") (pinfunction "2_2") (pintype "passive"))
      (node (ref "L3") (pin "1") (pinfunction "1_1") (pintype "passive"))
    )
    (net (code "62") (name "Net-(C29-P$1)") (class "Default")
      (node (ref "C29") (pin "1") (pinfunction "P$1_1") (pintype "passive"))
      (node (ref "D2") (pin "1") (pinfunction "A_1") (pintype "bidirectional"))
      (node (ref "L4") (pin "1") (pinfunction "1_1") (pintype "bidirectional"))
      (node (ref "U4") (pin "6") (pinfunction "SW_6") (pintype "output"))
    )
    (net (code "63") (name "Net-(C29-P$2)") (class "Default")
      (node (ref "C29") (pin "2") (pinfunction "P$2_2") (pintype "passive"))
      (node (ref "D1") (pin "-") (pinfunction "-_-") (pintype "passive"))
      (node (ref "U4") (pin "1") (pinfunction "BOOST_1") (pintype "input"))
    )
    (net (code "64") (name "Net-(D1-Pad+)") (class "Default")
      (node (ref "D1") (pin "+") (pinfunction "+_+") (pintype "passive"))
      (node (ref "R16") (pin "2") (pinfunction "2_2") (pintype "passive"))
    )
    (net (code "65") (name "Net-(J1-PadD+)") (class "Default")
      (node (ref "J1") (pin "D+") (pinfunction "D+_D+") (pintype "bidirectional"))
      (node (ref "R14") (pin "2") (pinfunction "2_2") (pintype "passive"))
    )
    (net (code "66") (name "Net-(J1-PadD-)") (class "Default")
      (node (ref "J1") (pin "D-") (pinfunction "D-_D-") (pintype "bidirectional"))
      (node (ref "R13") (pin "2") (pinfunction "2_2") (pintype "passive"))
    )
    (net (code "67") (name "Net-(LED1-PadA)") (class "Default")
      (node (ref "LED1") (pin "A") (pinfunction "A_A") (pintype "passive"))
      (node (ref "R3") (pin "2") (pinfunction "2_2") (pintype "passive"))
    )
    (net (code "68") (name "Net-(LED2-PadA)") (class "Default")
      (node (ref "LED2") (pin "A") (pinfunction "A_A") (pintype "passive"))
      (node (ref "R9") (pin "2") (pinfunction "2_2") (pintype "passive"))
    )
    (net (code "69") (name "Net-(RN3-Pad1)") (class "Default")
      (node (ref "RN3") (pin "1") (pinfunction "1_1") (pintype "passive"))
      (node (ref "RX") (pin "A") (pinfunction "A_A") (pintype "passive"))
    )
    (net (code "70") (name "Net-(RN3B-1)") (class "Default")
      (node (ref "RN3") (pin "2") (pinfunction "1_2") (pintype "passive"))
      (node (ref "TX") (pin "A") (pinfunction "A_A") (pintype "passive"))
    )
    (net (code "71") (name "Net-(RN3C-1)") (class "Default")
      (node (ref "L") (pin "A") (pinfunction "A_A") (pintype "passive"))
      (node (ref "RN3") (pin "3") (pinfunction "1_3") (pintype "passive"))
    )
    (net (code "72") (name "Net-(RN3D-1)") (class "Default")
      (node (ref "ON") (pin "A") (pinfunction "A_A") (pintype "passive"))
      (node (ref "RN3") (pin "4") (pinfunction "1_4") (pintype "passive"))
    )
    (net (code "73") (name "Net-(U1-ADVREF)") (class "Default")
      (node (ref "C19") (pin "2") (pinfunction "2_2") (pintype "passive"))
      (node (ref "L3") (pin "2") (pinfunction "2_2") (pintype "passive"))
      (node (ref "U1") (pin "75") (pinfunction "ADVREF_75") (pintype "power_in"))
    )
    (net (code "74") (name "Net-(U1-DFSDM)") (class "Default")
      (node (ref "R5") (pin "2") (pinfunction "2_2") (pintype "passive"))
      (node (ref "U1") (pin "43") (pinfunction "DFSDM_43") (pintype "input"))
    )
    (net (code "75") (name "Net-(U1-DFSDP)") (class "Default")
      (node (ref "R6") (pin "2") (pinfunction "2_2") (pintype "passive"))
      (node (ref "U1") (pin "42") (pinfunction "DFSDP_42") (pintype "input"))
    )
    (net (code "76") (name "Net-(U1-FWUP)") (class "Default")
      (node (ref "R4") (pin "1") (pinfunction "1_1") (pintype "passive"))
      (node (ref "U1") (pin "53") (pinfunction "FWUP_53") (pintype "input"))
    )
    (net (code "77") (name "Net-(U1-TST)") (class "Default")
      (node (ref "R8") (pin "2") (pinfunction "2_2") (pintype "passive"))
      (node (ref "U1") (pin "51") (pinfunction "TST_51") (pintype "input"))
    )
    (net (code "78") (name "Net-(U1-VBG)") (class "Default")
      (node (ref "C25") (pin "1") (pinfunction "1_1") (pintype "passive"))
      (node (ref "R7") (pin "2") (pinfunction "2_2") (pintype "passive"))
      (node (ref "U1") (pin "40") (pinfunction "VBG_40") (pintype "passive"))
    )
    (net (code "79") (name "Net-(U2-D+)") (class "Default")
      (node (ref "R14") (pin "1") (pinfunction "1_1") (pintype "passive"))
      (node (ref "U2") (pin "29") (pinfunction "D+_29") (pintype "bidirectional"))
    )
    (net (code "80") (name "Net-(U2-D-)") (class "Default")
      (node (ref "R13") (pin "1") (pinfunction "1_1") (pintype "passive"))
      (node (ref "U2") (pin "30") (pinfunction "D-_30") (pintype "bidirectional"))
    )
    (net (code "81") (name "Net-(U2-PB4)") (class "Default")
      (node (ref "SJ1") (pin "1") (pinfunction "1_1") (pintype "passive"))
      (node (ref "U2") (pin "18") (pinfunction "PB4_18") (pintype "bidirectional"))
    )
    (net (code "82") (name "Net-(U2-PB5)") (class "Default")
      (node (ref "SJ2") (pin "1") (pinfunction "1_1") (pintype "passive"))
      (node (ref "U2") (pin "19") (pinfunction "PB5_19") (pintype "bidirectional"))
    )
    (net (code "83") (name "Net-(U2-PB6)") (class "Default")
      (node (ref "SJ1") (pin "2") (pinfunction "2_2") (pintype "passive"))
      (node (ref "U2") (pin "20") (pinfunction "PB6_20") (pintype "bidirectional"))
    )
    (net (code "84") (name "Net-(U2-PB7)") (class "Default")
      (node (ref "SJ2") (pin "2") (pinfunction "2_2") (pintype "passive"))
      (node (ref "U2") (pin "21") (pinfunction "PB7_21") (pintype "bidirectional"))
    )
    (net (code "85") (name "Net-(U2-PC4)") (class "Default")
      (node (ref "R11") (pin "1") (pinfunction "1_1") (pintype "passive"))
      (node (ref "U2") (pin "26") (pinfunction "PC4_26") (pintype "bidirectional"))
    )
    (net (code "86") (name "Net-(U2-PD7)") (class "Default")
      (node (ref "R2") (pin "1") (pinfunction "1_1") (pintype "passive"))
      (node (ref "U2") (pin "13") (pinfunction "PD7_13") (pintype "bidirectional"))
    )
    (net (code "87") (name "Net-(U4-EN)") (class "Default")
      (node (ref "R15") (pin "1") (pinfunction "1_1") (pintype "passive"))
      (node (ref "U4") (pin "4") (pinfunction "EN_4") (pintype "input"))
    )
    (net (code "88") (name "Net-(U4-FB)") (class "Default")
      (node (ref "R16") (pin "1") (pinfunction "1_1") (pintype "passive"))
      (node (ref "R17") (pin "2") (pinfunction "2_2") (pintype "passive"))
      (node (ref "U4") (pin "3") (pinfunction "FB_3") (pintype "input"))
    )
    (net (code "89") (name "PIN22") (class "Default")
      (node (ref "U1") (pin "1") (pinfunction "PB26_1") (pintype "bidirectional"))
    )
    (net (code "90") (name "PIN23") (class "Default")
      (node (ref "U1") (pin "7") (pinfunction "PA14_7") (pintype "bidirectional"))
    )
    (net (code "91") (name "PIN24") (class "Default")
      (node (ref "U1") (pin "8") (pinfunction "PA15_8") (pintype "bidirectional"))
    )
    (net (code "92") (name "PIN25") (class "Default")
      (node (ref "U1") (pin "13") (pinfunction "PD0_13") (pintype "bidirectional"))
    )
    (net (code "93") (name "PIN26") (class "Default")
      (node (ref "U1") (pin "14") (pinfunction "PD1_14") (pintype "bidirectional"))
    )
    (net (code "94") (name "PIN27") (class "Default")
      (node (ref "U1") (pin "15") (pinfunction "PD2_15") (pintype "bidirectional"))
    )
    (net (code "95") (name "PIN28") (class "Default")
      (node (ref "U1") (pin "16") (pinfunction "PD3_16") (pintype "bidirectional"))
    )
    (net (code "96") (name "PIN29") (class "Default")
      (node (ref "U1") (pin "19") (pinfunction "PD6_19") (pintype "bidirectional"))
    )
    (net (code "97") (name "PIN30") (class "Default")
      (node (ref "U1") (pin "22") (pinfunction "PD9_22") (pintype "bidirectional"))
    )
    (net (code "98") (name "PIN31") (class "Default")
      (node (ref "U1") (pin "26") (pinfunction "PA7_26") (pintype "bidirectional"))
    )
    (net (code "99") (name "PIN32") (class "Default")
      (node (ref "U1") (pin "32") (pinfunction "PD10_32") (pintype "bidirectional"))
    )
    (net (code "100") (name "PIN33") (class "Default")
      (node (ref "U1") (pin "55") (pinfunction "PC1_55") (pintype "bidirectional"))
    )
    (net (code "101") (name "PIN34") (class "Default")
      (node (ref "U1") (pin "59") (pinfunction "PC2_59") (pintype "bidirectional"))
    )
    (net (code "102") (name "PIN35") (class "Default")
      (node (ref "U1") (pin "60") (pinfunction "PC3_60") (pintype "bidirectional"))
    )
    (net (code "103") (name "PIN36") (class "Default")
      (node (ref "U1") (pin "116") (pinfunction "PC4_116") (pintype "bidirectional"))
    )
    (net (code "104") (name "PIN37") (class "Default")
      (node (ref "U1") (pin "63") (pinfunction "PC5_63") (pintype "bidirectional"))
    )
    (net (code "105") (name "PIN38") (class "Default")
      (node (ref "U1") (pin "64") (pinfunction "PC6_64") (pintype "bidirectional"))
    )
    (net (code "106") (name "PIN39") (class "Default")
      (node (ref "U1") (pin "65") (pinfunction "PC7_65") (pintype "bidirectional"))
    )
    (net (code "107") (name "PIN40") (class "Default")
      (node (ref "U1") (pin "66") (pinfunction "PC8_66") (pintype "bidirectional"))
    )
    (net (code "108") (name "PIN41") (class "Default")
      (node (ref "U1") (pin "67") (pinfunction "PC9_67") (pintype "bidirectional"))
    )
    (net (code "109") (name "PIN42") (class "Default")
      (node (ref "U1") (pin "71") (pinfunction "PA19_71") (pintype "bidirectional"))
    )
    (net (code "110") (name "PIN43") (class "Default")
      (node (ref "U1") (pin "72") (pinfunction "PA20_72") (pintype "bidirectional"))
    )
    (net (code "111") (name "PIN44") (class "Default")
      (node (ref "U1") (pin "101") (pinfunction "PC19_101") (pintype "bidirectional"))
    )
    (net (code "112") (name "PIN45") (class "Default")
      (node (ref "U1") (pin "100") (pinfunction "PC18_100") (pintype "bidirectional"))
    )
    (net (code "113") (name "PIN46") (class "Default")
      (node (ref "U1") (pin "99") (pinfunction "PC17_99") (pintype "bidirectional"))
    )
    (net (code "114") (name "PIN47") (class "Default")
      (node (ref "U1") (pin "98") (pinfunction "PC16_98") (pintype "bidirectional"))
    )
    (net (code "115") (name "PIN48") (class "Default")
      (node (ref "U1") (pin "97") (pinfunction "PC15_97") (pintype "bidirectional"))
    )
    (net (code "116") (name "PIN49") (class "Default")
      (node (ref "U1") (pin "96") (pinfunction "PC14_96") (pintype "bidirectional"))
    )
    (net (code "117") (name "PIN50") (class "Default")
      (node (ref "U1") (pin "95") (pinfunction "PC13_95") (pintype "bidirectional"))
    )
    (net (code "118") (name "PIN51") (class "Default")
      (node (ref "U1") (pin "94") (pinfunction "PC12_94") (pintype "bidirectional"))
    )
    (net (code "119") (name "PWM2") (class "Default")
      (node (ref "U1") (pin "144") (pinfunction "PB25_144") (pintype "bidirectional"))
    )
    (net (code "120") (name "PWM3") (class "Default")
      (node (ref "U1") (pin "139") (pinfunction "PC28_139") (pintype "bidirectional"))
    )
    (net (code "121") (name "PWM5") (class "Default")
      (node (ref "U1") (pin "136") (pinfunction "PC25_136") (pintype "bidirectional"))
    )
    (net (code "122") (name "PWM6") (class "Default")
      (node (ref "U1") (pin "135") (pinfunction "PC24_135") (pintype "bidirectional"))
    )
    (net (code "123") (name "PWM7") (class "Default")
      (node (ref "U1") (pin "134") (pinfunction "PC23_134") (pintype "bidirectional"))
    )
    (net (code "124") (name "PWM8") (class "Default")
      (node (ref "U1") (pin "133") (pinfunction "PC22_133") (pintype "bidirectional"))
    )
    (net (code "125") (name "PWM9") (class "Default")
      (node (ref "U1") (pin "132") (pinfunction "PC21_132") (pintype "bidirectional"))
    )
    (net (code "126") (name "PWM11") (class "Default")
      (node (ref "U1") (pin "20") (pinfunction "PD7_20") (pintype "bidirectional"))
    )
    (net (code "127") (name "PWM12") (class "Default")
      (node (ref "U1") (pin "21") (pinfunction "PD8_21") (pintype "bidirectional"))
    )
    (net (code "128") (name "PWM13") (class "Default")
      (node (ref "IC1") (pin "3") (pinfunction "+IN_3") (pintype "input"))
      (node (ref "U1") (pin "68") (pinfunction "PB27_68") (pintype "bidirectional"))
    )
    (net (code "129") (name "RX") (class "Default")
      (node (ref "U1") (pin "27") (pinfunction "PA8_27") (pintype "bidirectional"))
      (node (ref "U3") (pin "4") (pinfunction "Y_4") (pintype "output"))
    )
    (net (code "130") (name "RXD0") (class "Default")
      (node (ref "U1") (pin "18") (pinfunction "PD5_18") (pintype "bidirectional"))
    )
    (net (code "131") (name "RXD1") (class "Default")
      (node (ref "U1") (pin "5") (pinfunction "PA12_5") (pintype "bidirectional"))
    )
    (net (code "132") (name "RXD2") (class "Default")
      (node (ref "U1") (pin "3") (pinfunction "PA10_3") (pintype "bidirectional"))
    )
    (net (code "133") (name "RXL") (class "Default")
      (node (ref "RX") (pin "C") (pinfunction "C_C") (pintype "passive"))
      (node (ref "U1") (pin "103") (pinfunction "PC30_103") (pintype "bidirectional"))
    )
    (net (code "134") (name "SCL0-3") (class "Default")
      (node (ref "RN5") (pin "5") (pinfunction "2_5") (pintype "passive"))
      (node (ref "U1") (pin "87") (pinfunction "PB13_87") (pintype "bidirectional"))
    )
    (net (code "135") (name "SCL1") (class "Default")
      (node (ref "U1") (pin "70") (pinfunction "PA18_70") (pintype "bidirectional"))
    )
    (net (code "136") (name "SDA0-3") (class "Default")
      (node (ref "RN5") (pin "6") (pinfunction "2_6") (pintype "passive"))
      (node (ref "U1") (pin "86") (pinfunction "PB12_86") (pintype "bidirectional"))
    )
    (net (code "137") (name "SDA1") (class "Default")
      (node (ref "U1") (pin "9") (pinfunction "PA17_9") (pintype "bidirectional"))
    )
    (net (code "138") (name "SPCK") (class "Default")
      (node (ref "U1") (pin "110") (pinfunction "PA27_110") (pintype "bidirectional"))
    )
    (net (code "139") (name "SS0{slash}PWM10") (class "Default")
      (node (ref "U1") (pin "102") (pinfunction "PC29_102") (pintype "bidirectional"))
      (node (ref "U1") (pin "111") (pinfunction "PA28_111") (pintype "bidirectional"))
    )
    (net (code "140") (name "SS1{slash}PWM4") (class "Default")
      (node (ref "U1") (pin "112") (pinfunction "PA29_112") (pintype "bidirectional"))
      (node (ref "U1") (pin "137") (pinfunction "PC26_137") (pintype "bidirectional"))
    )
    (net (code "141") (name "SS3") (class "Default")
      (node (ref "U1") (pin "142") (pinfunction "PB23_142") (pintype "bidirectional"))
    )
    (net (code "142") (name "TX") (class "Default")
      (node (ref "U1") (pin "2") (pinfunction "PA9_2") (pintype "bidirectional"))
      (node (ref "U2") (pin "8") (pinfunction "PD2_8") (pintype "bidirectional"))
    )
    (net (code "143") (name "TXD0") (class "Default")
      (node (ref "U1") (pin "17") (pinfunction "PD4_17") (pintype "bidirectional"))
    )
    (net (code "144") (name "TXD1") (class "Default")
      (node (ref "U1") (pin "6") (pinfunction "PA13_6") (pintype "bidirectional"))
    )
    (net (code "145") (name "TXD2") (class "Default")
      (node (ref "U1") (pin "4") (pinfunction "PA11_4") (pintype "bidirectional"))
    )
    (net (code "146") (name "TXL") (class "Default")
      (node (ref "TX") (pin "C") (pinfunction "C_C") (pintype "passive"))
      (node (ref "U1") (pin "107") (pinfunction "PA21_107") (pintype "bidirectional"))
    )
    (net (code "147") (name "UOTGID") (class "Default")
      (node (ref "U1") (pin "129") (pinfunction "PB11_129") (pintype "bidirectional"))
    )
    (net (code "148") (name "UOTGVBOF") (class "Default")
      (node (ref "U1") (pin "128") (pinfunction "PB10_128") (pintype "bidirectional"))
    )
    (net (code "149") (name "USBVCC") (class "Default")
      (node (ref "R11") (pin "2") (pinfunction "2_2") (pintype "passive"))
    )
    (net (code "150") (name "USBVCCU2") (class "Default")
      (node (ref "C28") (pin "2") (pinfunction "2_2") (pintype "passive"))
      (node (ref "F1") (pin "2") (pinfunction "2_2") (pintype "passive"))
      (node (ref "U2") (pin "31") (pinfunction "UVCC_31") (pintype "power_in"))
    )
    (net (code "151") (name "VDDANA") (class "Default")
      (node (ref "C10") (pin "2") (pinfunction "2_2") (pintype "passive"))
      (node (ref "C3") (pin "+") (pinfunction "+_+") (pintype "passive"))
      (node (ref "L1") (pin "2") (pinfunction "2_2") (pintype "passive"))
      (node (ref "U1") (pin "73") (pinfunction "VDDANA_73") (pintype "power_in"))
    )
    (net (code "152") (name "VDDOUTMI") (class "Default")
      (node (ref "C2") (pin "+") (pinfunction "+_+") (pintype "passive"))
      (node (ref "C9") (pin "2") (pinfunction "2_2") (pintype "passive"))
      (node (ref "L2") (pin "2") (pinfunction "2_2") (pintype "passive"))
      (node (ref "U1") (pin "41") (pinfunction "VDDUTMI_41") (pintype "input"))
    )
    (net (code "153") (name "XTAL1U2") (class "Default")
      (node (ref "R12") (pin "2") (pinfunction "2_2") (pintype "passive"))
      (node (ref "U$9") (pin "3") (pinfunction "3_3") (pintype "passive"))
      (node (ref "U2") (pin "1") (pinfunction "XTAL1_1") (pintype "input"))
    )
    (net (code "154") (name "XTAL2U2") (class "Default")
      (node (ref "R12") (pin "1") (pinfunction "1_1") (pintype "passive"))
      (node (ref "U$9") (pin "1") (pinfunction "1_1") (pintype "passive"))
      (node (ref "U2") (pin "2") (pinfunction "PC0_2") (pintype "bidirectional"))
    )
    (net (code "155") (name "XUSB") (class "Default")
      (node (ref "U1") (pin "39") (pinfunction "VBUS_39") (pintype "power_in"))
    )
    (net (code "156") (name "unconnected-(CN2-Pad7)") (class "Default")
      (node (ref "CN2") (pin "7") (pinfunction "7_7") (pintype "passive"))
    )
    (net (code "157") (name "unconnected-(J1-PadID)") (class "Default")
      (node (ref "J1") (pin "ID") (pinfunction "ID_ID") (pintype "bidirectional"))
    )
    (net (code "158") (name "unconnected-(RN5-Pad1)") (class "Default")
      (node (ref "RN5") (pin "1") (pinfunction "1_1") (pintype "passive"))
    )
    (net (code "159") (name "unconnected-(RN5A-2-Pad8)") (class "Default")
      (node (ref "RN5") (pin "8") (pinfunction "2_8") (pintype "passive"))
    )
    (net (code "160") (name "unconnected-(RN5B-1-Pad2)") (class "Default")
      (node (ref "RN5") (pin "2") (pinfunction "1_2") (pintype "passive"))
    )
    (net (code "161") (name "unconnected-(RN5B-2-Pad7)") (class "Default")
      (node (ref "RN5") (pin "7") (pinfunction "2_7") (pintype "passive"))
    )
    (net (code "162") (name "unconnected-(U1-NRST-Pad69)") (class "Default")
      (node (ref "U1") (pin "69") (pinfunction "NRST_69") (pintype "bidirectional"))
    )
    (net (code "163") (name "unconnected-(U1-PB22-Pad141)") (class "Default")
      (node (ref "U1") (pin "141") (pinfunction "PB22_141") (pintype "bidirectional"))
    )
    (net (code "164") (name "unconnected-(U1-PB24-Pad143)") (class "Default")
      (node (ref "U1") (pin "143") (pinfunction "PB24_143") (pintype "bidirectional"))
    )
    (net (code "165") (name "unconnected-(U1-PC10-Pad117)") (class "Default")
      (node (ref "U1") (pin "117") (pinfunction "PC10_117") (pintype "bidirectional"))
    )
    (net (code "166") (name "unconnected-(U1-PC11-Pad93)") (class "Default")
      (node (ref "U1") (pin "93") (pinfunction "PC11_93") (pintype "bidirectional"))
    )
    (net (code "167") (name "unconnected-(U1-PC20-Pad131)") (class "Default")
      (node (ref "U1") (pin "131") (pinfunction "PC20_131") (pintype "bidirectional"))
    )
    (net (code "168") (name "unconnected-(U1-PC27-Pad138)") (class "Default")
      (node (ref "U1") (pin "138") (pinfunction "PC27_138") (pintype "bidirectional"))
    )
    (net (code "169") (name "unconnected-(U1-SHDN-Pad50)") (class "Default")
      (node (ref "U1") (pin "50") (pinfunction "SHDN_50") (pintype "output"))
    )
    (net (code "170") (name "unconnected-(U2-PB0-Pad14)") (class "Default")
      (node (ref "U2") (pin "14") (pinfunction "PB0_14") (pintype "bidirectional"))
    )
    (net (code "171") (name "unconnected-(U2-PB1-Pad15)") (class "Default")
      (node (ref "U2") (pin "15") (pinfunction "PB1_15") (pintype "bidirectional"))
    )
    (net (code "172") (name "unconnected-(U2-PB2-Pad16)") (class "Default")
      (node (ref "U2") (pin "16") (pinfunction "PB2_16") (pintype "bidirectional"))
    )
    (net (code "173") (name "unconnected-(U2-PB3-Pad17)") (class "Default")
      (node (ref "U2") (pin "17") (pinfunction "PB3_17") (pintype "bidirectional"))
    )
    (net (code "174") (name "unconnected-(U2-PC1{slash}{slash}~{RESET}-Pad24)") (class "Default")
      (node (ref "U2") (pin "24") (pinfunction "PC1//~{RESET}_24") (pintype "bidirectional"))
    )
    (net (code "175") (name "unconnected-(U2-PC2-Pad5)") (class "Default")
      (node (ref "U2") (pin "5") (pinfunction "PC2_5") (pintype "bidirectional"))
    )
    (net (code "176") (name "unconnected-(U2-PC5-Pad25)") (class "Default")
      (node (ref "U2") (pin "25") (pinfunction "PC5_25") (pintype "bidirectional"))
    )
    (net (code "177") (name "unconnected-(U2-PD0-Pad6)") (class "Default")
      (node (ref "U2") (pin "6") (pinfunction "PD0_6") (pintype "bidirectional"))
    )
    (net (code "178") (name "unconnected-(U2-PD1-Pad7)") (class "Default")
      (node (ref "U2") (pin "7") (pinfunction "PD1_7") (pintype "bidirectional"))
    )
    (net (code "179") (name "unconnected-(U2-PD6-Pad12)") (class "Default")
      (node (ref "U2") (pin "12") (pinfunction "PD6_12") (pintype "bidirectional"))
    )
  )
)
